# bus_breakout.net
KiCad netlist of a schematic drawn in EAGLE
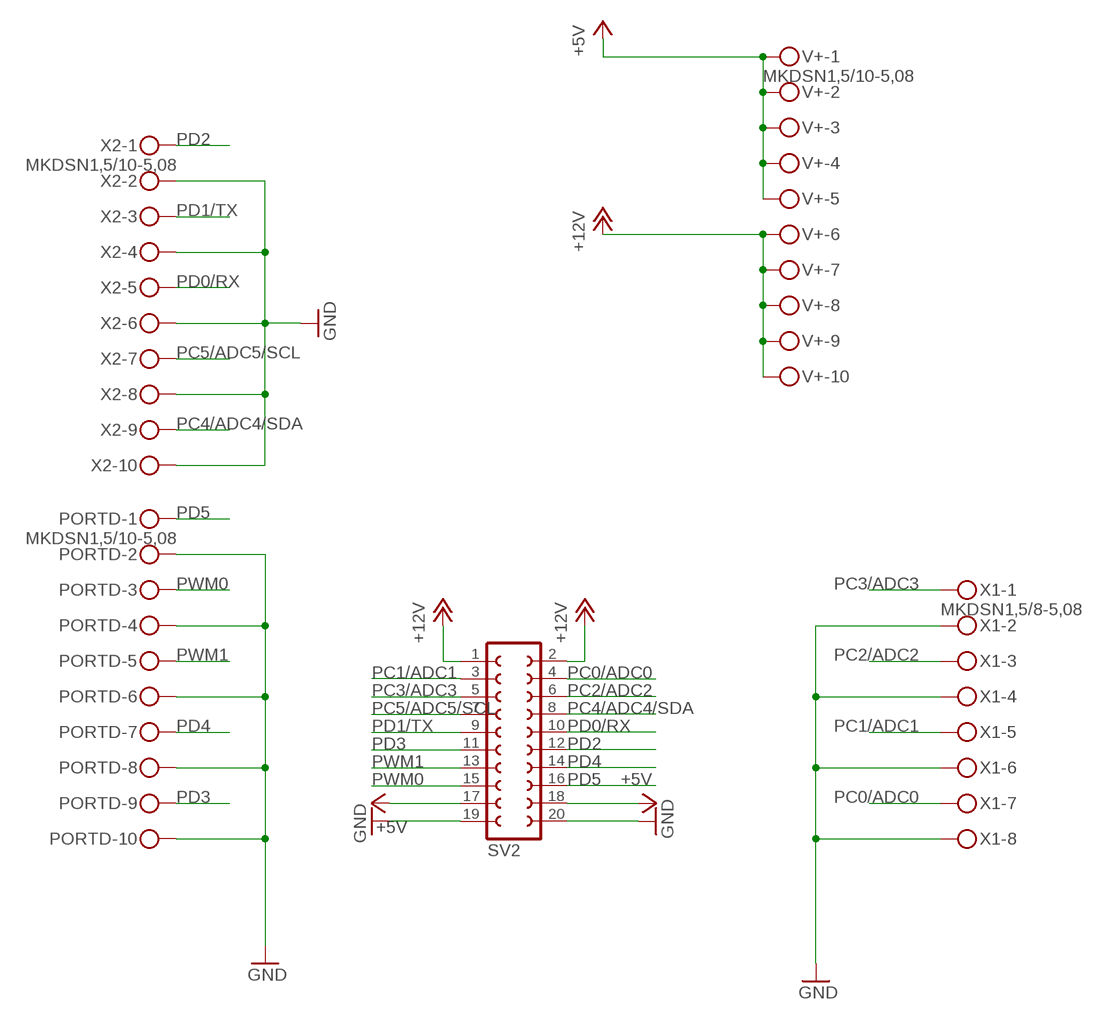
[diagram p0: schematic, sheet 1]

(export (version "E")
  (design (tool "Eeschema 10.0.6"))
  (components
    (comp (ref "PORTD")
      (value "MKDSN1,5/10-5,08")
      (footprint "eagle-import:MKDSN1,5_10-5,08")
      (fields (field (name "MPN") "SMKDSN1,5/10-5,08"))
      (libsource (lib "eagle-import") (part "MKDSN1,5/10-5,08"))
    )
    (comp (ref "SV2")
      (value "FE10-2")
      (footprint "eagle-import:FE10-2")
      (libsource (lib "eagle-import") (part "FE10-2"))
    )
    (comp (ref "V+")
      (value "MKDSN1,5/10-5,08")
      (footprint "eagle-import:MKDSN1,5_10-5,08")
      (fields
        (field (name "MPN") "SMKDSN1,5/10-5,08")
        (field (name "MPN_1") "SMKDSN1,5/10-5,08")
        (field (name "OC_FARNELL") "1792913")
        (field (name "OC_NEWARK") "70R0297")
      )
      (libsource (lib "eagle-import") (part "MKDSN1,5/10-5,08"))
    )
    (comp (ref "X1")
      (value "MKDSN1,5/8-5,08")
      (footprint "eagle-import:MKDSN1,5_8-5,08")
      (fields (field (name "MPN") "SMKDSN1,5/8-5,08"))
      (libsource (lib "eagle-import") (part "MKDSN1,5/8-5,08"))
    )
    (comp (ref "X2")
      (value "MKDSN1,5/10-5,08")
      (footprint "eagle-import:MKDSN1,5_10-5,08")
      (fields (field (name "MPN") "SMKDSN1,5/10-5,08"))
      (libsource (lib "eagle-import") (part "MKDSN1,5/10-5,08"))
    )
  )
  (nets
    (net (code "1") (name "+5V") (class "Default")
      (node (ref "SV2") (pin "17") (pinfunction "17_17") (pintype "passive"))
      (node (ref "SV2") (pin "18") (pinfunction "18_18") (pintype "passive"))
      (node (ref "V+") (pin "1") (pinfunction "KL_1") (pintype "passive"))
      (node (ref "V+") (pin "2") (pinfunction "KL_2") (pintype "passive"))
      (node (ref "V+") (pin "3") (pinfunction "KL_3") (pintype "passive"))
      (node (ref "V+") (pin "4") (pinfunction "KL_4") (pintype "passive"))
      (node (ref "V+") (pin "5") (pinfunction "KL_5") (pintype "passive"))
    )
    (net (code "2") (name "+12V") (class "Default")
      (node (ref "SV2") (pin "1") (pinfunction "1_1") (pintype "passive"))
      (node (ref "SV2") (pin "2") (pinfunction "2_2") (pintype "passive"))
      (node (ref "V+") (pin "10") (pinfunction "KL_10") (pintype "passive"))
      (node (ref "V+") (pin "6") (pinfunction "KL_6") (pintype "passive"))
      (node (ref "V+") (pin "7") (pinfunction "KL_7") (pintype "passive"))
      (node (ref "V+") (pin "8") (pinfunction "KL_8") (pintype "passive"))
      (node (ref "V+") (pin "9") (pinfunction "KL_9") (pintype "passive"))
    )
    (net (code "3") (name "/PC0{slash}ADC0") (class "Default")
      (node (ref "SV2") (pin "4") (pinfunction "4_4") (pintype "passive"))
      (node (ref "X1") (pin "7") (pinfunction "KL_7") (pintype "passive"))
    )
    (net (code "4") (name "/PC1{slash}ADC1") (class "Default")
      (node (ref "SV2") (pin "3") (pinfunction "3_3") (pintype "passive"))
      (node (ref "X1") (pin "5") (pinfunction "KL_5") (pintype "passive"))
    )
    (net (code "5") (name "/PC2{slash}ADC2") (class "Default")
      (node (ref "SV2") (pin "6") (pinfunction "6_6") (pintype "passive"))
      (node (ref "X1") (pin "3") (pinfunction "KL_3") (pintype "passive"))
    )
    (net (code "6") (name "/PC3{slash}ADC3") (class "Default")
      (node (ref "SV2") (pin "5") (pinfunction "5_5") (pintype "passive"))
      (node (ref "X1") (pin "1") (pinfunction "KL_1") (pintype "passive"))
    )
    (net (code "7") (name "/PC4{slash}ADC4{slash}SDA") (class "Default")
      (node (ref "SV2") (pin "8") (pinfunction "8_8") (pintype "passive"))
      (node (ref "X2") (pin "9") (pinfunction "KL_9") (pintype "passive"))
    )
    (net (code "8") (name "/PC5{slash}ADC5{slash}SCL") (class "Default")
      (node (ref "SV2") (pin "7") (pinfunction "7_7") (pintype "passive"))
      (node (ref "X2") (pin "7") (pinfunction "KL_7") (pintype "passive"))
    )
    (net (code "9") (name "/PD0{slash}RX") (class "Default")
      (node (ref "SV2") (pin "10") (pinfunction "10_10") (pintype "passive"))
      (node (ref "X2") (pin "5") (pinfunction "KL_5") (pintype "passive"))
    )
    (net (code "10") (name "/PD1{slash}TX") (class "Default")
      (node (ref "SV2") (pin "9") (pinfunction "9_9") (pintype "passive"))
      (node (ref "X2") (pin "3") (pinfunction "KL_3") (pintype "passive"))
    )
    (net (code "11") (name "/PD2") (class "Default")
      (node (ref "SV2") (pin "12") (pinfunction "12_12") (pintype "passive"))
      (node (ref "X2") (pin "1") (pinfunction "KL_1") (pintype "passive"))
    )
    (net (code "12") (name "/PD3") (class "Default")
      (node (ref "PORTD") (pin "9") (pinfunction "KL_9") (pintype "passive"))
      (node (ref "SV2") (pin "11") (pinfunction "11_11") (pintype "passive"))
    )
    (net (code "13") (name "/PD4") (class "Default")
      (node (ref "PORTD") (pin "7") (pinfunction "KL_7") (pintype "passive"))
      (node (ref "SV2") (pin "14") (pinfunction "14_14") (pintype "passive"))
    )
    (net (code "14") (name "/PD5") (class "Default")
      (node (ref "PORTD") (pin "1") (pinfunction "KL_1") (pintype "passive"))
      (node (ref "SV2") (pin "16") (pinfunction "16_16") (pintype "passive"))
    )
    (net (code "15") (name "/PWM0") (class "Default")
      (node (ref "PORTD") (pin "3") (pinfunction "KL_3") (pintype "passive"))
      (node (ref "SV2") (pin "15") (pinfunction "15_15") (pintype "passive"))
    )
    (net (code "16") (name "/PWM1") (class "Default")
      (node (ref "PORTD") (pin "5") (pinfunction "KL_5") (pintype "passive"))
      (node (ref "SV2") (pin "13") (pinfunction "13_13") (pintype "passive"))
    )
    (net (code "17") (name "GND") (class "Default")
      (node (ref "PORTD") (pin "10") (pinfunction "KL_10") (pintype "passive"))
      (node (ref "PORTD") (pin "2") (pinfunction "KL_2") (pintype "passive"))
      (node (ref "PORTD") (pin "4") (pinfunction "KL_4") (pintype "passive"))
      (node (ref "PORTD") (pin "6") (pinfunction "KL_6") (pintype "passive"))
      (node (ref "PORTD") (pin "8") (pinfunction "KL_8") (pintype "passive"))
      (node (ref "SV2") (pin "19") (pinfunction "19_19") (pintype "passive"))
      (node (ref "SV2") (pin "20") (pinfunction "20_20") (pintype "passive"))
      (node (ref "X1") (pin "2") (pinfunction "KL_2") (pintype "passive"))
      (node (ref "X1") (pin "4") (pinfunction "KL_4") (pintype "passive"))
      (node (ref "X1") (pin "6") (pinfunction "KL_6") (pintype "passive"))
      (node (ref "X1") (pin "8") (pinfunction "KL_8") (pintype "passive"))
      (node (ref "X2") (pin "10") (pinfunction "KL_10") (pintype "passive"))
      (node (ref "X2") (pin "2") (pinfunction "KL_2") (pintype "passive"))
      (node (ref "X2") (pin "4") (pinfunction "KL_4") (pintype "passive"))
      (node (ref "X2") (pin "6") (pinfunction "KL_6") (pintype "passive"))
      (node (ref "X2") (pin "8") (pinfunction "KL_8") (pintype "passive"))
    )
  )
)
